# ProDoc_Schematic1_2025-12-02.net
KiCad netlist of a schematic drawn in EasyEDA Pro
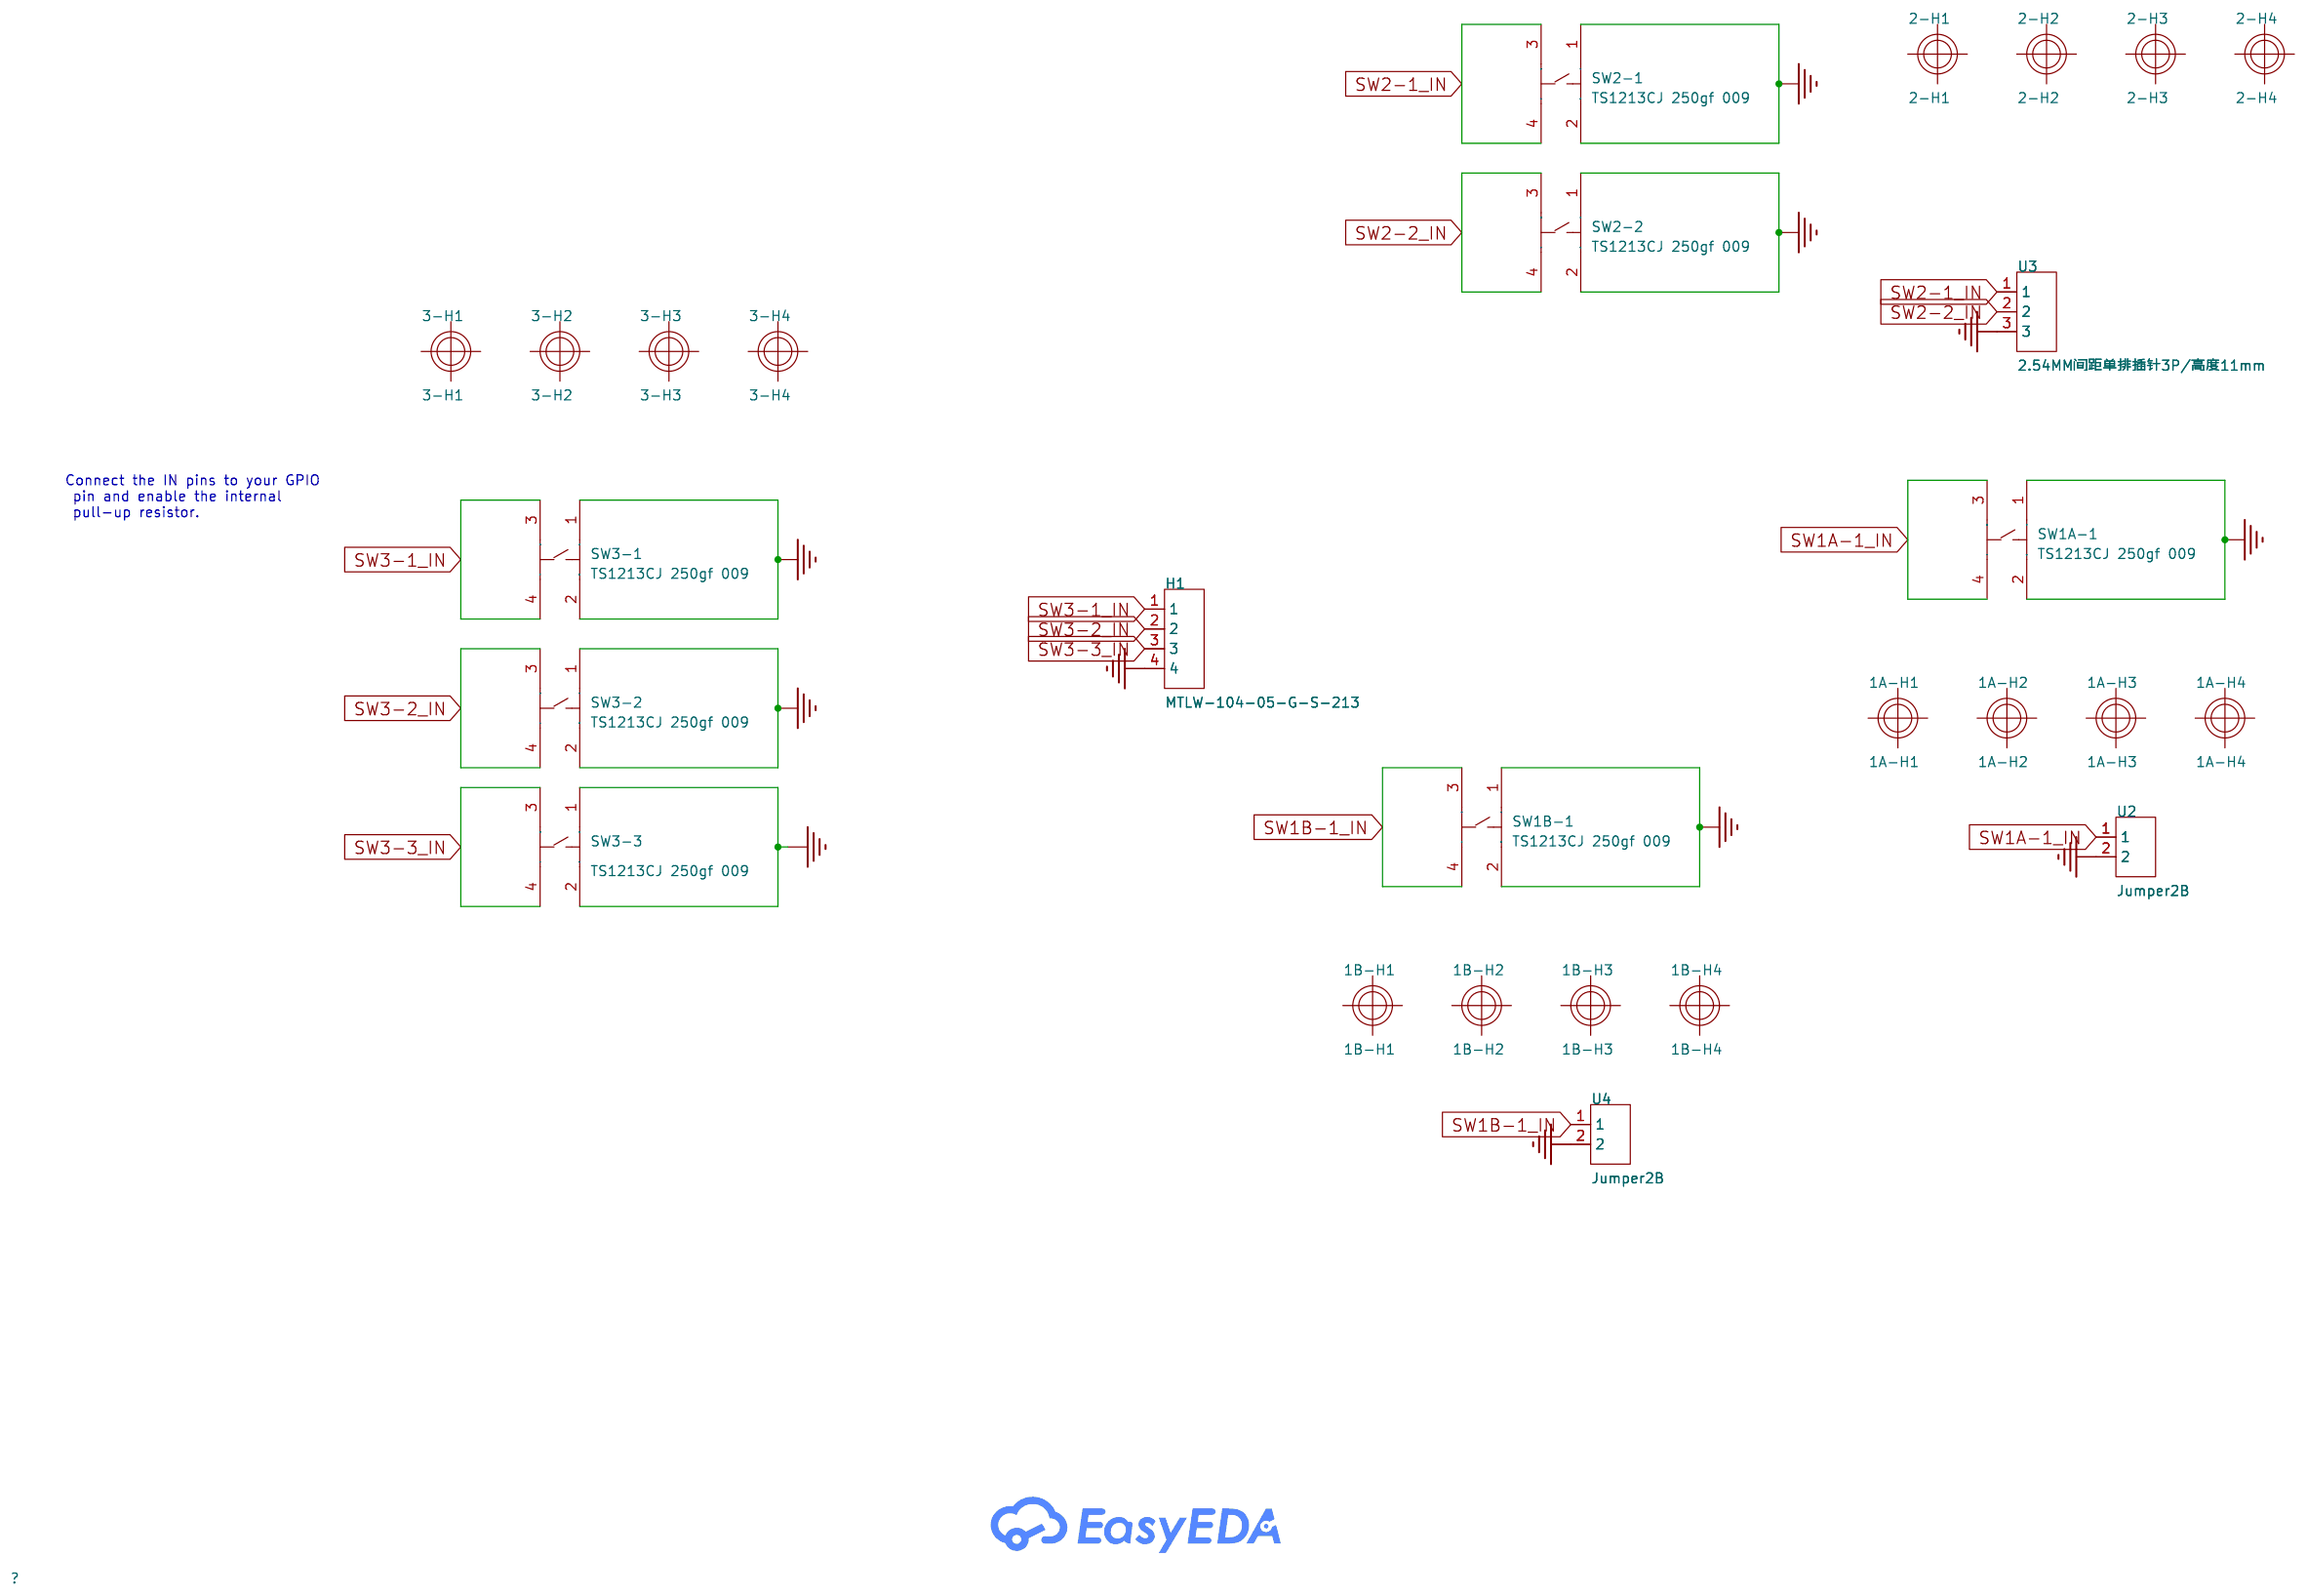
[diagram p0: schematic sheet]

(export (version "E")
  (design (tool "Eeschema 10.0.6"))
  (components
    (comp (ref "1A-H1")
      (value "1A-H1")
      (footprint "easyedapro:MOUNTING_HOLE_3MM")
      (libsource (lib "easyedapro") (part "MOUNTING_HOLE_3MM"))
    )
    (comp (ref "1A-H2")
      (value "1A-H2")
      (footprint "easyedapro:MOUNTING_HOLE_3MM")
      (libsource (lib "easyedapro") (part "MOUNTING_HOLE_3MM"))
    )
    (comp (ref "1A-H3")
      (value "1A-H3")
      (footprint "easyedapro:MOUNTING_HOLE_3MM")
      (libsource (lib "easyedapro") (part "MOUNTING_HOLE_3MM"))
    )
    (comp (ref "1A-H4")
      (value "1A-H4")
      (footprint "easyedapro:MOUNTING_HOLE_3MM")
      (libsource (lib "easyedapro") (part "MOUNTING_HOLE_3MM"))
    )
    (comp (ref "1B-H1")
      (value "1B-H1")
      (footprint "easyedapro:MOUNTING_HOLE_3MM")
      (libsource (lib "easyedapro") (part "MOUNTING_HOLE_3MM"))
    )
    (comp (ref "1B-H2")
      (value "1B-H2")
      (footprint "easyedapro:MOUNTING_HOLE_3MM")
      (libsource (lib "easyedapro") (part "MOUNTING_HOLE_3MM"))
    )
    (comp (ref "1B-H3")
      (value "1B-H3")
      (footprint "easyedapro:MOUNTING_HOLE_3MM")
      (libsource (lib "easyedapro") (part "MOUNTING_HOLE_3MM"))
    )
    (comp (ref "1B-H4")
      (value "1B-H4")
      (footprint "easyedapro:MOUNTING_HOLE_3MM")
      (libsource (lib "easyedapro") (part "MOUNTING_HOLE_3MM"))
    )
    (comp (ref "2-H1")
      (value "2-H1")
      (footprint "easyedapro:MOUNTING_HOLE_3MM")
      (libsource (lib "easyedapro") (part "MOUNTING_HOLE_3MM"))
    )
    (comp (ref "2-H2")
      (value "2-H2")
      (footprint "easyedapro:MOUNTING_HOLE_3MM")
      (libsource (lib "easyedapro") (part "MOUNTING_HOLE_3MM"))
    )
    (comp (ref "2-H3")
      (value "2-H3")
      (footprint "easyedapro:MOUNTING_HOLE_3MM")
      (libsource (lib "easyedapro") (part "MOUNTING_HOLE_3MM"))
    )
    (comp (ref "2-H4")
      (value "2-H4")
      (footprint "easyedapro:MOUNTING_HOLE_3MM")
      (libsource (lib "easyedapro") (part "MOUNTING_HOLE_3MM"))
    )
    (comp (ref "3-H1")
      (value "3-H1")
      (footprint "easyedapro:MOUNTING_HOLE_3MM")
      (libsource (lib "easyedapro") (part "MOUNTING_HOLE_3MM"))
    )
    (comp (ref "3-H2")
      (value "3-H2")
      (footprint "easyedapro:MOUNTING_HOLE_3MM")
      (libsource (lib "easyedapro") (part "MOUNTING_HOLE_3MM"))
    )
    (comp (ref "3-H3")
      (value "3-H3")
      (footprint "easyedapro:MOUNTING_HOLE_3MM")
      (libsource (lib "easyedapro") (part "MOUNTING_HOLE_3MM"))
    )
    (comp (ref "3-H4")
      (value "3-H4")
      (footprint "easyedapro:MOUNTING_HOLE_3MM")
      (libsource (lib "easyedapro") (part "MOUNTING_HOLE_3MM"))
    )
    (comp (ref "H1")
      (value "MTLW-104-05-G-S-213")
      (footprint "easyedapro:HDR-TH_4P-P2.54_MTLW-104-05-G-S-165")
      (fields (field (name "Manufacturer") "SAMTEC"))
      (libsource (lib "easyedapro") (part "MTLW-104-05-G-S-213"))
    )
    (comp (ref "SW1A-1")
      (value "TS1213CJ 250gf 009")
      (footprint "easyedapro:KEY-TH_4P-L12.0-W12.0-P5.00-LS12.5")
      (fields (field (name "Manufacturer") "SHOU HAN(首韩)"))
      (libsource (lib "easyedapro") (part "TS1213CJ 250GF 009"))
    )
    (comp (ref "SW1B-1")
      (value "TS1213CJ 250gf 009")
      (footprint "easyedapro:KEY-TH_4P-L12.0-W12.0-P5.00-LS12.5")
      (fields (field (name "Manufacturer") "SHOU HAN(首韩)"))
      (libsource (lib "easyedapro") (part "TS1213CJ 250GF 009"))
    )
    (comp (ref "SW2-1")
      (value "TS1213CJ 250gf 009")
      (footprint "easyedapro:KEY-TH_4P-L12.0-W12.0-P5.00-LS12.5")
      (fields (field (name "Manufacturer") "SHOU HAN(首韩)"))
      (libsource (lib "easyedapro") (part "TS1213CJ 250GF 009"))
    )
    (comp (ref "SW2-2")
      (value "TS1213CJ 250gf 009")
      (footprint "easyedapro:KEY-TH_4P-L12.0-W12.0-P5.00-LS12.5")
      (fields (field (name "Manufacturer") "SHOU HAN(首韩)"))
      (libsource (lib "easyedapro") (part "TS1213CJ 250GF 009"))
    )
    (comp (ref "SW3-1")
      (value "TS1213CJ 250gf 009")
      (footprint "easyedapro:KEY-TH_4P-L12.0-W12.0-P5.00-LS12.5")
      (fields (field (name "Manufacturer") "SHOU HAN(首韩)"))
      (libsource (lib "easyedapro") (part "TS1213CJ 250GF 009"))
    )
    (comp (ref "SW3-2")
      (value "TS1213CJ 250gf 009")
      (footprint "easyedapro:KEY-TH_4P-L12.0-W12.0-P5.00-LS12.5")
      (fields (field (name "Manufacturer") "SHOU HAN(首韩)"))
      (libsource (lib "easyedapro") (part "TS1213CJ 250GF 009"))
    )
    (comp (ref "SW3-3")
      (value "TS1213CJ 250gf 009")
      (footprint "easyedapro:KEY-TH_4P-L12.0-W12.0-P5.00-LS12.5")
      (fields (field (name "Manufacturer") "SHOU HAN(首韩)"))
      (libsource (lib "easyedapro") (part "TS1213CJ 250GF 009"))
    )
    (comp (ref "U2")
      (value "Jumper2B")
      (footprint "easyedapro:HDR-TH_2P-P2.54-V-M-1")
      (libsource (lib "easyedapro") (part "JUMPER2"))
    )
    (comp (ref "U3")
      (value "2.54MM间距单排插针3P/高度11mm")
      (footprint "easyedapro:HDR-TH_3P-P2.54-V-M")
      (libsource (lib "easyedapro") (part "2.54MM间距单排插针3P/高度11MM"))
    )
    (comp (ref "U4")
      (value "Jumper2B")
      (footprint "easyedapro:HDR-TH_2P-P2.54-V-M-1")
      (libsource (lib "easyedapro") (part "JUMPER2"))
    )
  )
  (nets
    (net (code "1") (name "GND1A") (class "Default")
      (node (ref "SW1A-1") (pin "1") (pinfunction "1_1") (pintype "unspecified"))
      (node (ref "SW1A-1") (pin "2") (pinfunction "2_2") (pintype "unspecified"))
      (node (ref "U2") (pin "2") (pinfunction "2_2") (pintype "unspecified"))
    )
    (net (code "2") (name "GND1B") (class "Default")
      (node (ref "SW1B-1") (pin "1") (pinfunction "1_1") (pintype "unspecified"))
      (node (ref "SW1B-1") (pin "2") (pinfunction "2_2") (pintype "unspecified"))
      (node (ref "U4") (pin "2") (pinfunction "2_2") (pintype "unspecified"))
    )
    (net (code "3") (name "GND2") (class "Default")
      (node (ref "SW2-1") (pin "1") (pinfunction "1_1") (pintype "unspecified"))
      (node (ref "SW2-1") (pin "2") (pinfunction "2_2") (pintype "unspecified"))
      (node (ref "SW2-2") (pin "1") (pinfunction "1_1") (pintype "unspecified"))
      (node (ref "SW2-2") (pin "2") (pinfunction "2_2") (pintype "unspecified"))
      (node (ref "U3") (pin "3") (pinfunction "3_3") (pintype "unspecified"))
    )
    (net (code "4") (name "GND3") (class "Default")
      (node (ref "H1") (pin "4") (pinfunction "4_4") (pintype "unspecified"))
      (node (ref "SW3-1") (pin "1") (pinfunction "1_1") (pintype "unspecified"))
      (node (ref "SW3-1") (pin "2") (pinfunction "2_2") (pintype "unspecified"))
      (node (ref "SW3-2") (pin "1") (pinfunction "1_1") (pintype "unspecified"))
      (node (ref "SW3-2") (pin "2") (pinfunction "2_2") (pintype "unspecified"))
      (node (ref "SW3-3") (pin "1") (pinfunction "1_1") (pintype "unspecified"))
      (node (ref "SW3-3") (pin "2") (pinfunction "2_2") (pintype "unspecified"))
    )
    (net (code "5") (name "SW1A-1_IN") (class "Default")
      (node (ref "SW1A-1") (pin "3") (pinfunction "3_3") (pintype "unspecified"))
      (node (ref "SW1A-1") (pin "4") (pinfunction "4_4") (pintype "unspecified"))
      (node (ref "U2") (pin "1") (pinfunction "1_1") (pintype "unspecified"))
    )
    (net (code "6") (name "SW1B-1_IN") (class "Default")
      (node (ref "SW1B-1") (pin "3") (pinfunction "3_3") (pintype "unspecified"))
      (node (ref "SW1B-1") (pin "4") (pinfunction "4_4") (pintype "unspecified"))
      (node (ref "U4") (pin "1") (pinfunction "1_1") (pintype "unspecified"))
    )
    (net (code "7") (name "SW2-1_IN") (class "Default")
      (node (ref "SW2-1") (pin "3") (pinfunction "3_3") (pintype "unspecified"))
      (node (ref "SW2-1") (pin "4") (pinfunction "4_4") (pintype "unspecified"))
      (node (ref "U3") (pin "1") (pinfunction "1_1") (pintype "unspecified"))
    )
    (net (code "8") (name "SW2-2_IN") (class "Default")
      (node (ref "SW2-2") (pin "3") (pinfunction "3_3") (pintype "unspecified"))
      (node (ref "SW2-2") (pin "4") (pinfunction "4_4") (pintype "unspecified"))
      (node (ref "U3") (pin "2") (pinfunction "2_2") (pintype "unspecified"))
    )
    (net (code "9") (name "SW3-1_IN") (class "Default")
      (node (ref "H1") (pin "1") (pinfunction "1_1") (pintype "unspecified"))
      (node (ref "SW3-1") (pin "3") (pinfunction "3_3") (pintype "unspecified"))
      (node (ref "SW3-1") (pin "4") (pinfunction "4_4") (pintype "unspecified"))
    )
    (net (code "10") (name "SW3-2_IN") (class "Default")
      (node (ref "H1") (pin "2") (pinfunction "2_2") (pintype "unspecified"))
      (node (ref "SW3-2") (pin "3") (pinfunction "3_3") (pintype "unspecified"))
      (node (ref "SW3-2") (pin "4") (pinfunction "4_4") (pintype "unspecified"))
    )
    (net (code "11") (name "SW3-3_IN") (class "Default")
      (node (ref "H1") (pin "3") (pinfunction "3_3") (pintype "unspecified"))
      (node (ref "SW3-3") (pin "3") (pinfunction "3_3") (pintype "unspecified"))
      (node (ref "SW3-3") (pin "4") (pinfunction "4_4") (pintype "unspecified"))
    )
  )
)
